# POWER.net
KiCad netlist of a schematic drawn in Altium Designer
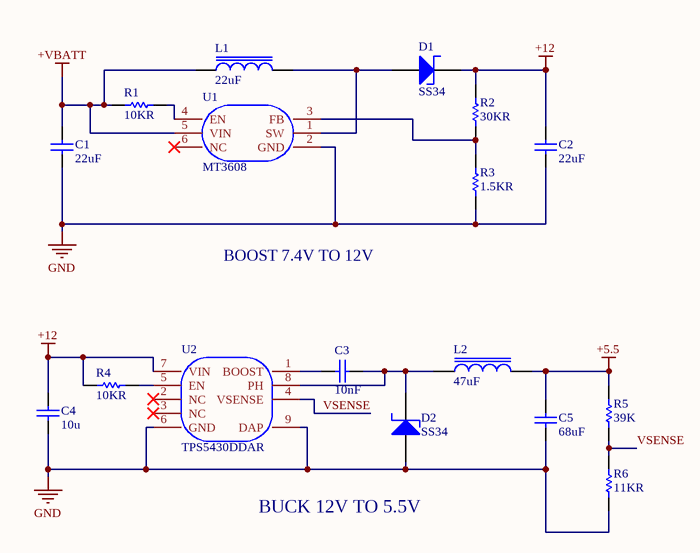
[diagram p0: POWER.SchDoc]

(export (version "E")
  (design (tool "Eeschema 10.0.6"))
  (components
    (comp (ref "C1")
      (value "22uF")
      (footprint "CAP_0805")
      (description "Tụ Gốm 0805 22uF 16V")
      (libsource (lib "Schlib1") (part "CAP_22U_0805"))
    )
    (comp (ref "C2")
      (value "22uF")
      (footprint "CAP_0805")
      (description "Tụ Gốm 0805 22uF 16V")
      (libsource (lib "Schlib1") (part "CAP_22U_0805"))
    )
    (comp (ref "C3")
      (value "10nF")
      (footprint "CAP_0805")
      (description "Tụ Gốm 0805 10nF 50V")
      (libsource (lib "Schlib1") (part "CAP_10n_0805"))
    )
    (comp (ref "C4")
      (value "10u")
      (description "Tụ Gốm 0805 10uF 25V")
      (libsource (lib "Schlib1") (part "CAP_10U_0805"))
    )
    (comp (ref "C5")
      (value "68uF")
      (footprint "CAP_0805")
      (description "Tụ Gốm 0805 68pF 50V")
      (libsource (lib "Schlib1") (part "CAP_68u_0805"))
    )
    (comp (ref "D1")
      (value "SS34")
      (footprint "DIO_SMA")
      (description "SS34 SMC Diode Schottky 3A")
      (libsource (lib "Schlib1") (part "DIO_SS34"))
    )
    (comp (ref "D2")
      (value "SS34")
      (footprint "DIO_SMA")
      (description "SS34 SMC Diode Schottky 3A")
      (libsource (lib "Schlib1") (part "DIO_SS34"))
    )
    (comp (ref "L1")
      (value "22uF")
      (footprint "IND_1280")
      (description "Cuộn Cảm Dán SMD CDRH127 1280-220 22uH 6.3A")
      (libsource (lib "Schlib1") (part "IND_22U_1280"))
    )
    (comp (ref "L2")
      (value "47uF")
      (footprint "IND_1280")
      (description "Cuộn Cảm Dán SMD CDRH127 1280-470 47uH 3.25A")
      (libsource (lib "Schlib1") (part "IND_47U_1280"))
    )
    (comp (ref "R1")
      (value "10KR")
      (footprint "RES_0805")
      (description "Điện Trở 10 KOhm 0805 1%")
      (libsource (lib "Schlib1") (part "RES_10K_0805"))
    )
    (comp (ref "R2")
      (value "30KR")
      (footprint "RES_0805")
      (description "Điện Trở 30 KOhm 0805 1%")
      (libsource (lib "Schlib1") (part "RES_30K_0805"))
    )
    (comp (ref "R3")
      (value "1.5KR")
      (footprint "RES_0805")
      (description "Điện Trở 1.5 KOhm 0805 1%")
      (libsource (lib "Schlib1") (part "RES_1.5K_0805"))
    )
    (comp (ref "R4")
      (value "10KR")
      (footprint "RES_0805")
      (description "Điện Trở 10 KOhm 0805 1%")
      (libsource (lib "Schlib1") (part "RES_10K_0805"))
    )
    (comp (ref "R5")
      (value "39K")
      (footprint "RES_0805")
      (description "Điện Trở 39 KOhm 0805 1%")
      (libsource (lib "Schlib1") (part "RES_39K_0805"))
    )
    (comp (ref "R6")
      (value "11KR")
      (footprint "RES_0402")
      (description "Điện Trở 11 KOhm 0402 5%")
      (libsource (lib "Schlib1") (part "RES_11K_0402"))
    )
    (comp (ref "U1")
      (value "MT3608")
      (footprint "MT3608")
      (description "MT3608 IC Điều Chỉnh Tăng Áp 2A SOT-23-6")
      (libsource (lib "Schlib1") (part "MT3608"))
    )
    (comp (ref "U2")
      (value "TPS5430DDAR")
      (footprint "TPS5430_8SOIC")
      (description "TPS5430DDAR IC Điều Chỉnh Giảm Áp 3A 8-SOIC")
      (libsource (lib "Schlib1") (part "TPS5430DDAR"))
    )
  )
  (nets
    (net (code "1") (name "+5.5") (class "Default")
      (node (ref "C5") (pin "2") (pinfunction "2_2") (pintype "passive"))
      (node (ref "L2") (pin "2") (pinfunction "2_2") (pintype "passive"))
      (node (ref "R5") (pin "2") (pinfunction "2_2") (pintype "passive"))
    )
    (net (code "2") (name "+12") (class "Default")
      (node (ref "C2") (pin "2") (pinfunction "2_2") (pintype "passive"))
      (node (ref "C4") (pin "2") (pinfunction "2_2") (pintype "passive"))
      (node (ref "D1") (pin "2") (pinfunction "K_2") (pintype "passive"))
      (node (ref "R2") (pin "2") (pinfunction "2_2") (pintype "passive"))
      (node (ref "R4") (pin "2") (pinfunction "2_2") (pintype "passive"))
      (node (ref "U2") (pin "7") (pinfunction "VIN_7") (pintype "passive"))
    )
    (net (code "3") (name "+VBATT") (class "Default")
      (node (ref "C1") (pin "2") (pinfunction "2_2") (pintype "passive"))
      (node (ref "L1") (pin "1") (pinfunction "1_1") (pintype "passive"))
      (node (ref "R1") (pin "2") (pinfunction "2_2") (pintype "passive"))
      (node (ref "U1") (pin "5") (pinfunction "VIN_5") (pintype "passive"))
    )
    (net (code "4") (name "/VSENSE") (class "Default")
      (node (ref "R5") (pin "1") (pinfunction "1_1") (pintype "passive"))
      (node (ref "R6") (pin "2") (pinfunction "2_2") (pintype "passive"))
      (node (ref "U2") (pin "4") (pinfunction "VSENSE_4") (pintype "passive"))
    )
    (net (code "5") (name "GND") (class "Default")
      (node (ref "C1") (pin "1") (pinfunction "1_1") (pintype "passive"))
      (node (ref "C2") (pin "1") (pinfunction "1_1") (pintype "passive"))
      (node (ref "C4") (pin "1") (pinfunction "1_1") (pintype "passive"))
      (node (ref "C5") (pin "1") (pinfunction "1_1") (pintype "passive"))
      (node (ref "D2") (pin "1") (pinfunction "A_1") (pintype "passive"))
      (node (ref "R3") (pin "1") (pinfunction "1_1") (pintype "passive"))
      (node (ref "R6") (pin "1") (pinfunction "1_1") (pintype "passive"))
      (node (ref "U1") (pin "2") (pinfunction "GND_2") (pintype "passive"))
      (node (ref "U2") (pin "6") (pinfunction "GND_6") (pintype "passive"))
      (node (ref "U2") (pin "9") (pinfunction "DAP_9") (pintype "passive"))
    )
    (net (code "6") (name "Net-(D1-A)") (class "Default")
      (node (ref "D1") (pin "1") (pinfunction "A_1") (pintype "passive"))
      (node (ref "L1") (pin "2") (pinfunction "2_2") (pintype "passive"))
      (node (ref "U1") (pin "1") (pinfunction "SW_1") (pintype "passive"))
    )
    (net (code "7") (name "Net-(D2-K)") (class "Default")
      (node (ref "C3") (pin "2") (pinfunction "2_2") (pintype "passive"))
      (node (ref "D2") (pin "2") (pinfunction "K_2") (pintype "passive"))
      (node (ref "L2") (pin "1") (pinfunction "1_1") (pintype "passive"))
      (node (ref "U2") (pin "8") (pinfunction "PH_8") (pintype "passive"))
    )
    (net (code "8") (name "Net-(U1-EN)") (class "Default")
      (node (ref "R1") (pin "1") (pinfunction "1_1") (pintype "passive"))
      (node (ref "U1") (pin "4") (pinfunction "EN_4") (pintype "passive"))
    )
    (net (code "9") (name "Net-(U1-FB)") (class "Default")
      (node (ref "R2") (pin "1") (pinfunction "1_1") (pintype "passive"))
      (node (ref "R3") (pin "2") (pinfunction "2_2") (pintype "passive"))
      (node (ref "U1") (pin "3") (pinfunction "FB_3") (pintype "passive"))
    )
    (net (code "10") (name "Net-(U2-BOOST)") (class "Default")
      (node (ref "C3") (pin "1") (pinfunction "1_1") (pintype "passive"))
      (node (ref "U2") (pin "1") (pinfunction "BOOST_1") (pintype "passive"))
    )
    (net (code "11") (name "Net-(U2-EN)") (class "Default")
      (node (ref "R4") (pin "1") (pinfunction "1_1") (pintype "passive"))
      (node (ref "U2") (pin "5") (pinfunction "EN_5") (pintype "passive"))
    )
    (net (code "12") (name "unconnected-(U1-NC-Pad6)") (class "Default")
      (node (ref "U1") (pin "6") (pinfunction "NC_6") (pintype "passive+no_connect"))
    )
    (net (code "13") (name "unconnected-(U2-NC-Pad2)") (class "Default")
      (node (ref "U2") (pin "2") (pinfunction "NC_2") (pintype "passive+no_connect"))
    )
    (net (code "14") (name "unconnected-(U2-NC-Pad3)") (class "Default")
      (node (ref "U2") (pin "3") (pinfunction "NC_3") (pintype "passive+no_connect"))
    )
  )
)
